# V4-AddOnSduino-V02-009.net
KiCad netlist of a schematic drawn in EAGLE
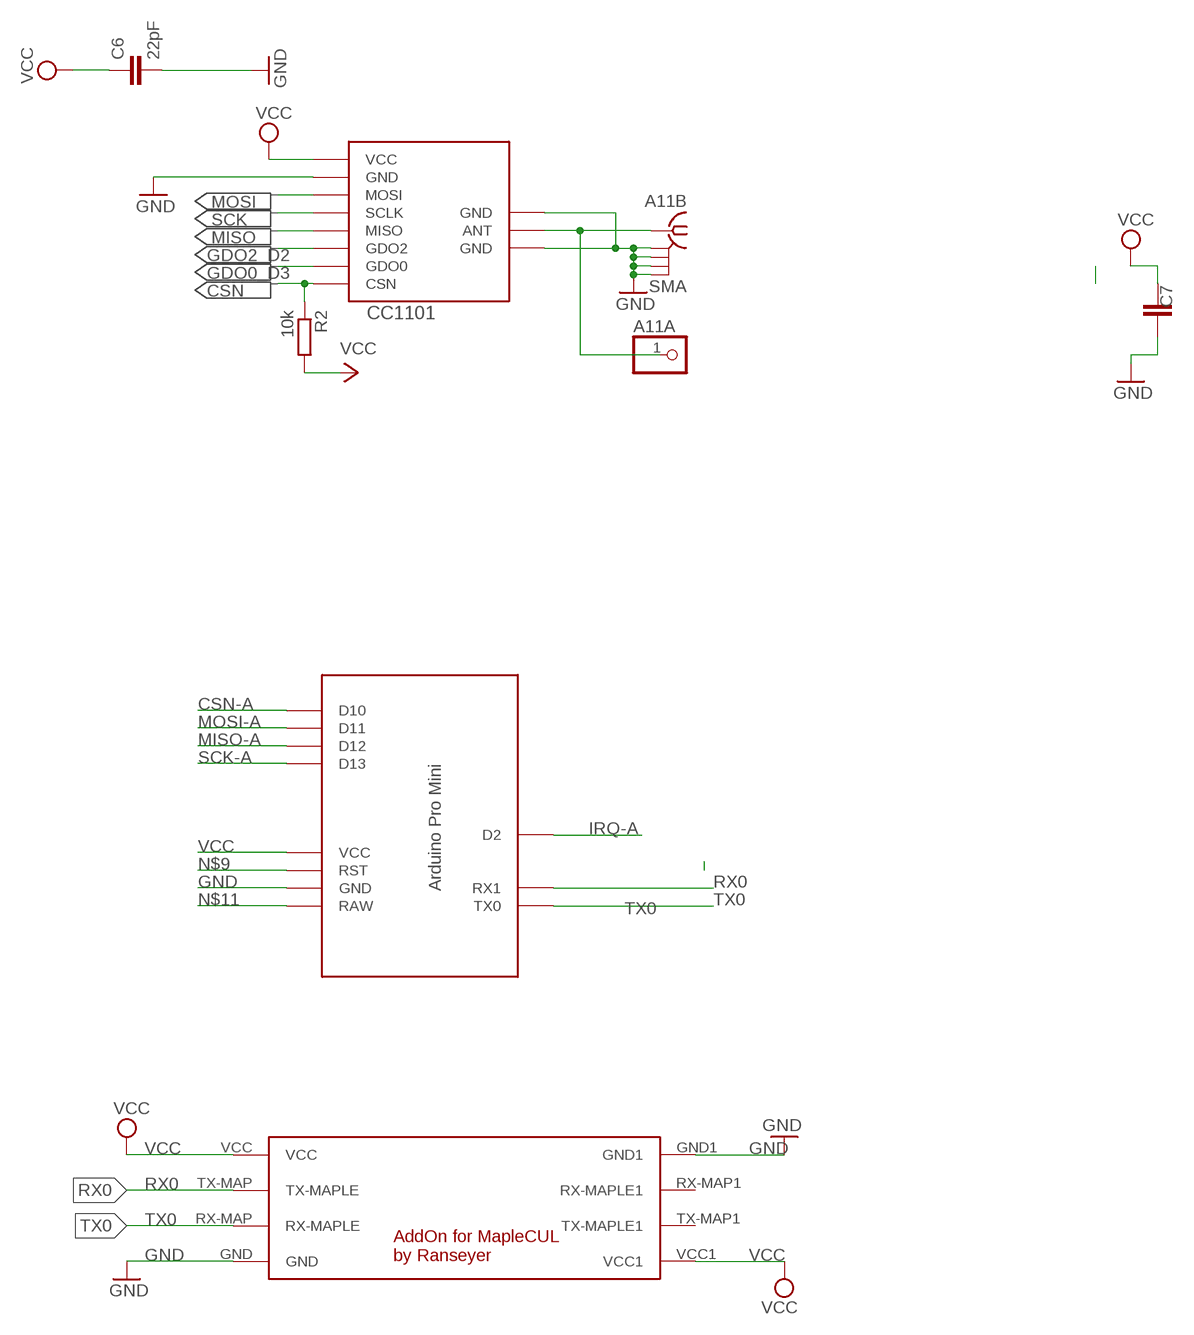
[diagram p0: schematic, sheet 1]

(export (version "E")
  (design (tool "Eeschema 10.0.6"))
  (components
    (comp (ref "A11A")
      (value "PINHD-1X1")
      (footprint "eagle-import:1X01")
      (libsource (lib "eagle-import") (part "PINHD-1X1"))
    )
    (comp (ref "A11B")
      (value "SMA")
      (footprint "eagle-import:SMA")
      (libsource (lib "eagle-import") (part "SMA"))
    )
    (comp (ref "C6")
      (value "22pF")
      (footprint "eagle-import:C0805")
      (libsource (lib "eagle-import") (part "C-EUC0805"))
    )
    (comp (ref "C7")
      (value "C-EUC1812")
      (footprint "eagle-import:C1812")
      (libsource (lib "eagle-import") (part "C-EUC1812"))
    )
    (comp (ref "CC1101")
      (value "CC1101_MODULE1SMD")
      (footprint "eagle-import:CC1101_MODULE1_SMD")
      (libsource (lib "eagle-import") (part "CC1101_MODULE1SMD"))
    )
    (comp (ref "R2")
      (value "10k")
      (footprint "eagle-import:M0805")
      (libsource (lib "eagle-import") (part "R-EU_M0805"))
    )
    (comp (ref "U$1")
      (value "MARTIN-PROMINI-SPI")
      (footprint "eagle-import:MARTIN-PRO-SPI")
      (libsource (lib "eagle-import") (part "MARTIN-PROMINI-SPI"))
    )
    (comp (ref "U$2")
      (value "MAPLE-CUL-ADDON-V01")
      (footprint "eagle-import:MAPLE-CUL-V01")
      (libsource (lib "eagle-import") (part "MAPLE-CUL-ADDON-V01"))
    )
  )
  (nets
    (net (code "1") (name "/CSN") (class "Default")
      (node (ref "CC1101") (pin "CSN") (pinfunction "CSN_CSN") (pintype "bidirectional"))
      (node (ref "R2") (pin "1") (pinfunction "1_1") (pintype "passive"))
    )
    (net (code "2") (name "/CSN-A") (class "Default")
      (node (ref "U$1") (pin "D10") (pinfunction "D10_D10") (pintype "bidirectional"))
    )
    (net (code "3") (name "/GDO0_D3") (class "Default")
      (node (ref "CC1101") (pin "GDO0") (pinfunction "GDO0_GDO0") (pintype "bidirectional"))
    )
    (net (code "4") (name "/GDO2_D2") (class "Default")
      (node (ref "CC1101") (pin "GDO2") (pinfunction "GDO2_GDO2") (pintype "bidirectional"))
    )
    (net (code "5") (name "/IRQ-A") (class "Default")
      (node (ref "U$1") (pin "D2") (pinfunction "D2_D2") (pintype "bidirectional"))
    )
    (net (code "6") (name "/MISO") (class "Default")
      (node (ref "CC1101") (pin "MISO") (pinfunction "MISO_MISO") (pintype "bidirectional"))
    )
    (net (code "7") (name "/MISO-A") (class "Default")
      (node (ref "U$1") (pin "D12") (pinfunction "D12_D12") (pintype "bidirectional"))
    )
    (net (code "8") (name "/MOSI") (class "Default")
      (node (ref "CC1101") (pin "MOSI") (pinfunction "MOSI_MOSI") (pintype "bidirectional"))
    )
    (net (code "9") (name "/MOSI-A") (class "Default")
      (node (ref "U$1") (pin "D11") (pinfunction "D11_D11") (pintype "bidirectional"))
    )
    (net (code "10") (name "/N$9") (class "Default")
      (node (ref "U$1") (pin "RST") (pinfunction "RST_RST") (pintype "bidirectional"))
    )
    (net (code "11") (name "/N$11") (class "Default")
      (node (ref "U$1") (pin "RAW") (pinfunction "RAW_RAW") (pintype "bidirectional"))
    )
    (net (code "12") (name "/SCK") (class "Default")
      (node (ref "CC1101") (pin "SCLK") (pinfunction "SCLK_SCLK") (pintype "bidirectional"))
    )
    (net (code "13") (name "/SCK-A") (class "Default")
      (node (ref "U$1") (pin "D13") (pinfunction "D13_D13") (pintype "bidirectional"))
    )
    (net (code "14") (name "GND") (class "Default")
      (node (ref "A11B") (pin "GND@1") (pinfunction "2_GND@1") (pintype "passive"))
      (node (ref "A11B") (pin "GND@2") (pinfunction "3_GND@2") (pintype "passive"))
      (node (ref "A11B") (pin "GND@3") (pinfunction "4_GND@3") (pintype "passive"))
      (node (ref "A11B") (pin "GND@4") (pinfunction "5_GND@4") (pintype "passive"))
      (node (ref "C6") (pin "2") (pinfunction "2_2") (pintype "passive"))
      (node (ref "C7") (pin "1") (pinfunction "1_1") (pintype "passive"))
      (node (ref "CC1101") (pin "GND@0") (pinfunction "GND_GND@0") (pintype "power_in"))
      (node (ref "CC1101") (pin "GND@1") (pinfunction "GND_GND@1") (pintype "power_in"))
      (node (ref "CC1101") (pin "GND@2") (pinfunction "GND_GND@2") (pintype "power_in"))
      (node (ref "U$1") (pin "GND") (pinfunction "GND_GND") (pintype "bidirectional"))
      (node (ref "U$2") (pin "GND") (pinfunction "GND_GND") (pintype "bidirectional"))
      (node (ref "U$2") (pin "GND1") (pinfunction "GND1_GND1") (pintype "bidirectional"))
    )
    (net (code "15") (name "Net-(A11A-Pad1)") (class "Default")
      (node (ref "A11A") (pin "1") (pinfunction "1_1") (pintype "passive"))
      (node (ref "A11B") (pin "1") (pinfunction "1_1") (pintype "passive"))
      (node (ref "CC1101") (pin "ANT") (pinfunction "ANT_ANT") (pintype "output"))
    )
    (net (code "16") (name "RX0") (class "Default")
      (node (ref "U$1") (pin "RX1") (pinfunction "RX1_RX1") (pintype "bidirectional"))
      (node (ref "U$2") (pin "TX-MAP") (pinfunction "TX-MAPLE_TX-MAP") (pintype "bidirectional"))
    )
    (net (code "17") (name "TX0") (class "Default")
      (node (ref "U$1") (pin "TX0") (pinfunction "TX0_TX0") (pintype "bidirectional"))
      (node (ref "U$2") (pin "RX-MAP") (pinfunction "RX-MAPLE_RX-MAP") (pintype "bidirectional"))
    )
    (net (code "18") (name "VCC") (class "Default")
      (node (ref "C6") (pin "1") (pinfunction "1_1") (pintype "passive"))
      (node (ref "C7") (pin "2") (pinfunction "2_2") (pintype "passive"))
      (node (ref "CC1101") (pin "VCC") (pinfunction "VCC_VCC") (pintype "power_in"))
      (node (ref "R2") (pin "2") (pinfunction "2_2") (pintype "passive"))
      (node (ref "U$1") (pin "VCC") (pinfunction "VCC_VCC") (pintype "bidirectional"))
      (node (ref "U$2") (pin "VCC") (pinfunction "VCC_VCC") (pintype "bidirectional"))
      (node (ref "U$2") (pin "VCC1") (pinfunction "VCC1_VCC1") (pintype "bidirectional"))
    )
    (net (code "19") (name "unconnected-(U$2-RX-MAPLE1-PadRX-MAP1)") (class "Default")
      (node (ref "U$2") (pin "RX-MAP1") (pinfunction "RX-MAPLE1_RX-MAP1") (pintype "bidirectional"))
    )
    (net (code "20") (name "unconnected-(U$2-TX-MAPLE1-PadTX-MAP1)") (class "Default")
      (node (ref "U$2") (pin "TX-MAP1") (pinfunction "TX-MAPLE1_TX-MAP1") (pintype "bidirectional"))
    )
  )
)
